# IntegratedSensor.net
KiCad netlist of a schematic drawn in EAGLE
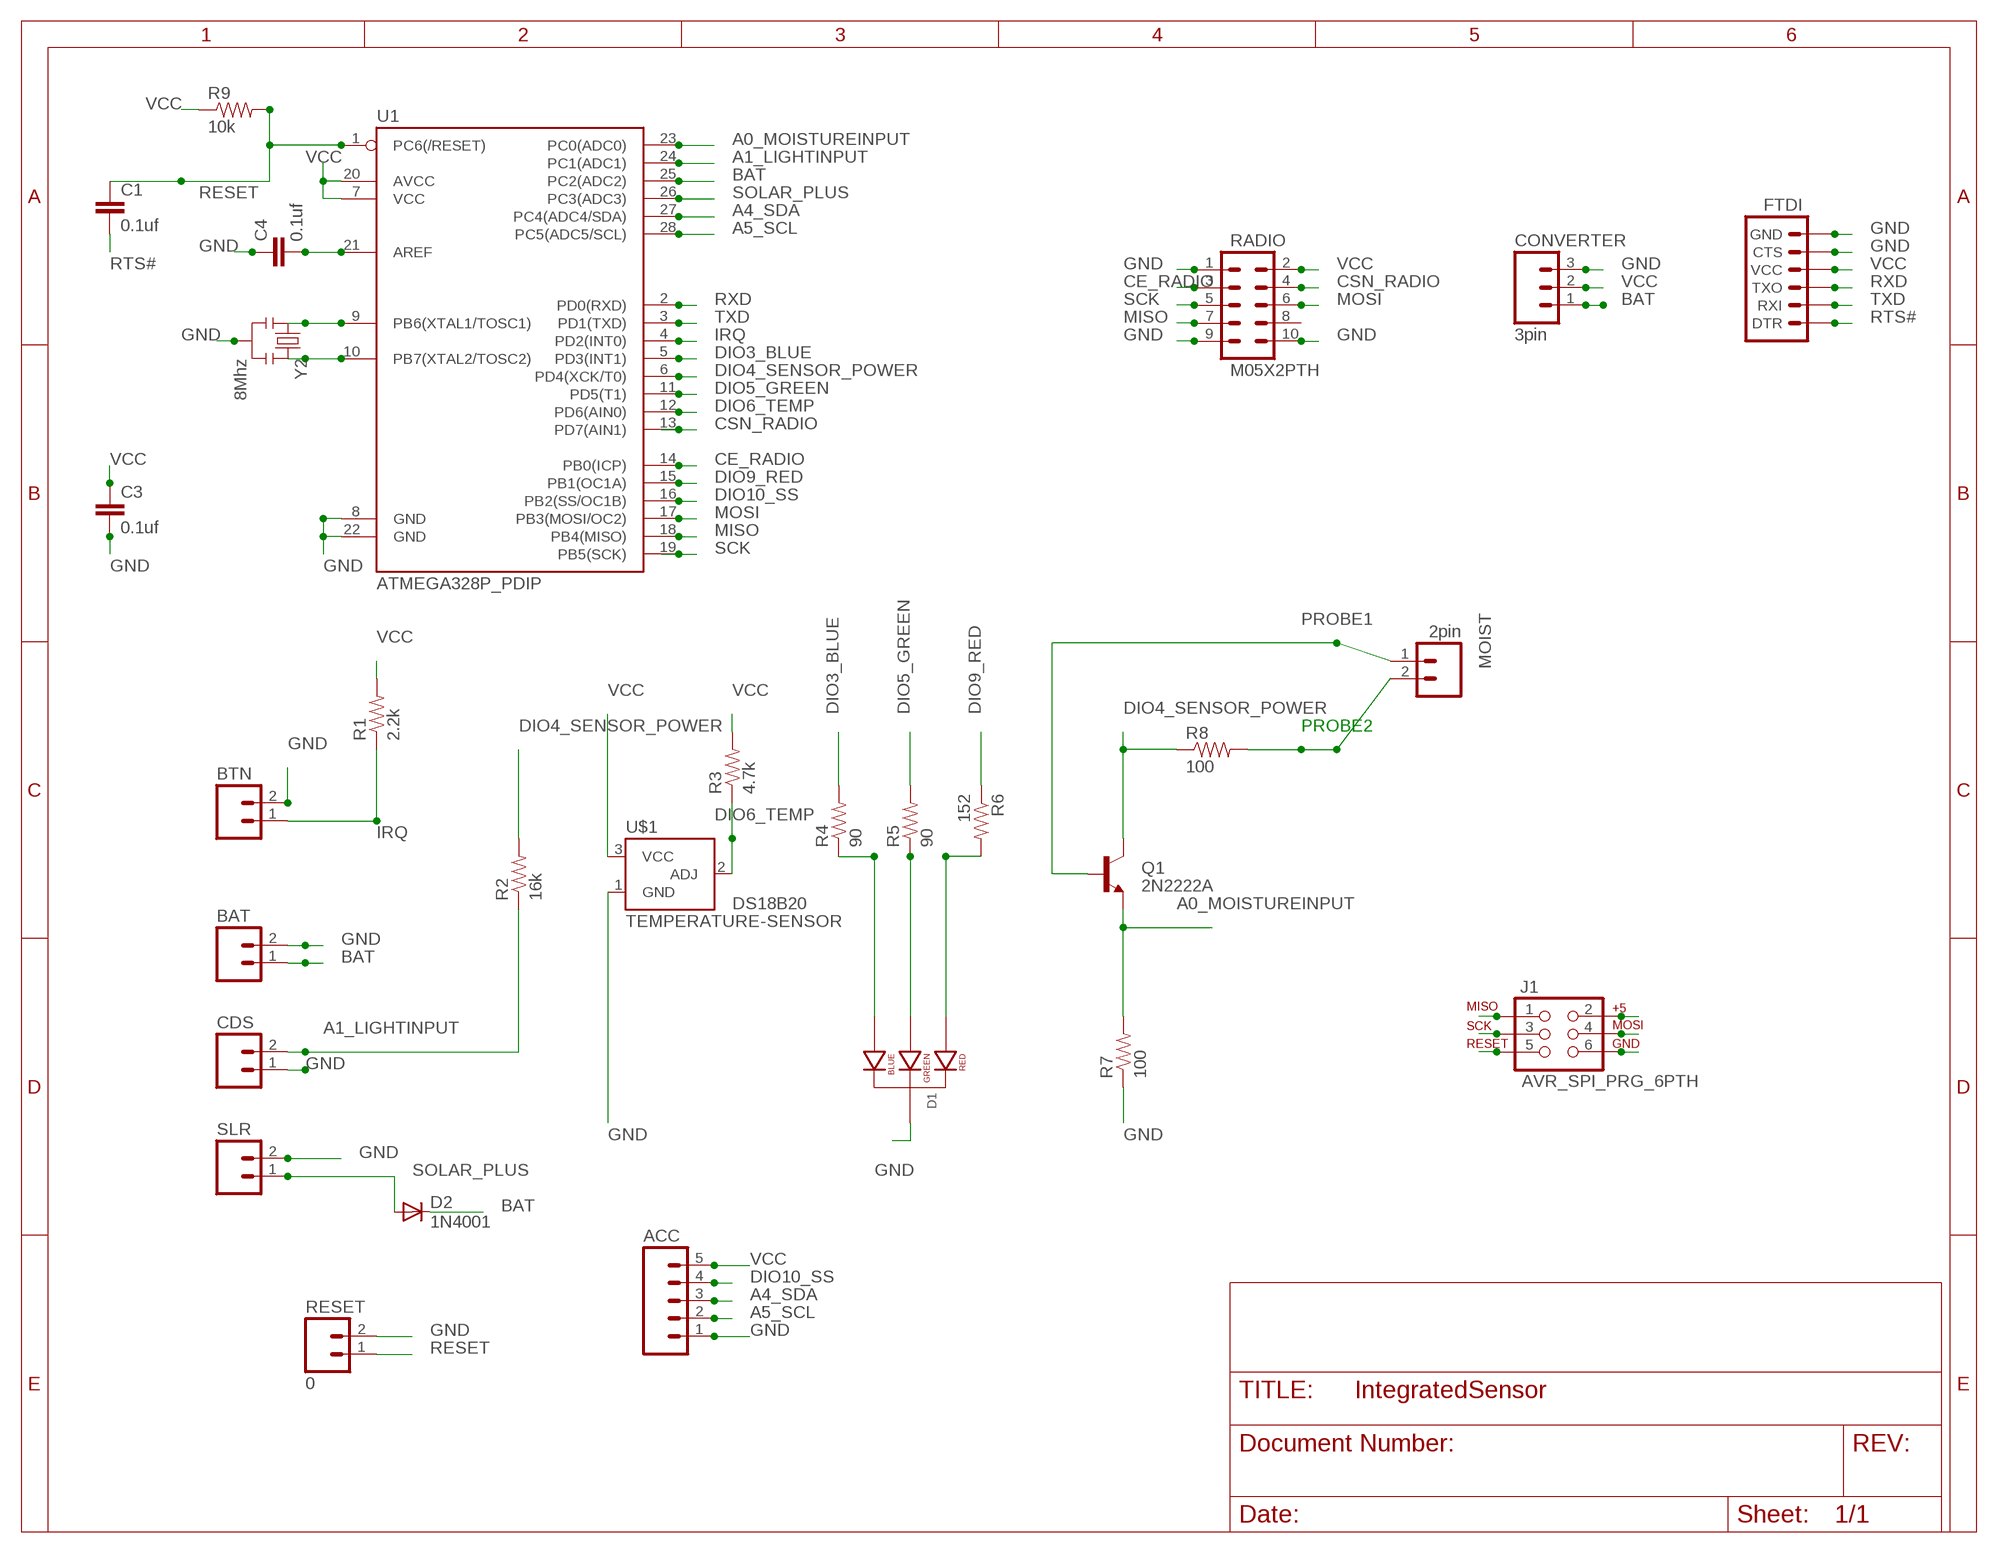
[diagram p0: schematic, sheet 1]

(export (version "E")
  (design (tool "Eeschema 10.0.6"))
  (components
    (comp (ref "ACC")
      (value "M05PTH")
      (footprint "eagle-import:1X05")
      (libsource (lib "eagle-import") (part "M05PTH"))
    )
    (comp (ref "BAT")
      (value "M02PTH")
      (footprint "eagle-import:1X02")
      (libsource (lib "eagle-import") (part "M02PTH"))
    )
    (comp (ref "BTN")
      (value "M02PTH")
      (footprint "eagle-import:1X02")
      (libsource (lib "eagle-import") (part "M02PTH"))
    )
    (comp (ref "C1")
      (value "0.1uf")
      (footprint "eagle-import:CAP-PTH-SMALL")
      (libsource (lib "eagle-import") (part "CAPPTH"))
    )
    (comp (ref "C3")
      (value "0.1uf")
      (footprint "eagle-import:CAP-PTH-SMALL")
      (libsource (lib "eagle-import") (part "CAPPTH"))
    )
    (comp (ref "C4")
      (value "0.1uf")
      (footprint "eagle-import:CAP-PTH-SMALL")
      (libsource (lib "eagle-import") (part "CAPPTH"))
    )
    (comp (ref "CDS")
      (value "M02PTH")
      (footprint "eagle-import:1X02")
      (libsource (lib "eagle-import") (part "M02PTH"))
    )
    (comp (ref "CONVERTER")
      (value "3pin")
      (footprint "eagle-import:1X03")
      (libsource (lib "eagle-import") (part "M03PTH"))
    )
    (comp (ref "D1")
      (value "LED-RGB-CC-THRUCLEAR")
      (footprint "eagle-import:LED-RGB-THRU")
      (libsource (lib "eagle-import") (part "LED-RGB-CC-THRUCLEAR"))
    )
    (comp (ref "D2")
      (value "1N4001")
      (footprint "eagle-import:DIODE-1N4001")
      (libsource (lib "eagle-import") (part "DIODEPTH"))
    )
    (comp (ref "FTDI")
      (value "ARDUINO_SERIAL_PROGRAMPTH")
      (footprint "eagle-import:1X06")
      (libsource (lib "eagle-import") (part "ARDUINO_SERIAL_PROGRAMPTH"))
    )
    (comp (ref "J1")
      (value "AVR_SPI_PRG_6PTH")
      (footprint "eagle-import:2X3")
      (libsource (lib "eagle-import") (part "AVR_SPI_PRG_6PTH"))
    )
    (comp (ref "MOIST")
      (value "2pin")
      (footprint "eagle-import:1X02")
      (libsource (lib "eagle-import") (part "M02PTH"))
    )
    (comp (ref "Q1")
      (value "2N2222A")
      (footprint "eagle-import:TO-92-AMMO")
      (libsource (lib "eagle-import") (part "TRANSISTOR_NPNTO-92-AMMO"))
    )
    (comp (ref "R1")
      (value "2.2k")
      (footprint "eagle-import:1_6W-RES")
      (libsource (lib "eagle-import") (part "RESISTORPTH-1/6W"))
    )
    (comp (ref "R2")
      (value "16k")
      (footprint "eagle-import:1_6W-RES")
      (libsource (lib "eagle-import") (part "RESISTORPTH-1/6W"))
    )
    (comp (ref "R3")
      (value "4.7k")
      (footprint "eagle-import:1_6W-RES")
      (libsource (lib "eagle-import") (part "RESISTORPTH-1/6W"))
    )
    (comp (ref "R4")
      (value "90")
      (footprint "eagle-import:1_6W-RES")
      (libsource (lib "eagle-import") (part "RESISTORPTH-1/6W"))
    )
    (comp (ref "R5")
      (value "90")
      (footprint "eagle-import:1_6W-RES")
      (libsource (lib "eagle-import") (part "RESISTORPTH-1/6W"))
    )
    (comp (ref "R6")
      (value "152")
      (footprint "eagle-import:1_6W-RES")
      (libsource (lib "eagle-import") (part "RESISTORPTH-1/6W"))
    )
    (comp (ref "R7")
      (value "100")
      (footprint "eagle-import:1_6W-RES")
      (libsource (lib "eagle-import") (part "RESISTORPTH-1/6W"))
    )
    (comp (ref "R8")
      (value "100")
      (footprint "eagle-import:1_6W-RES")
      (libsource (lib "eagle-import") (part "RESISTORPTH-1/6W"))
    )
    (comp (ref "R9")
      (value "10k")
      (footprint "eagle-import:1_6W-RES")
      (libsource (lib "eagle-import") (part "RESISTORPTH-1/6W"))
    )
    (comp (ref "RADIO")
      (value "M05X2PTH")
      (footprint "eagle-import:AVR_ICSP")
      (libsource (lib "eagle-import") (part "M05X2PTH"))
    )
    (comp (ref "RESET")
      (value "0")
      (footprint "eagle-import:1X02")
      (libsource (lib "eagle-import") (part "M02PTH"))
    )
    (comp (ref "SLR")
      (value "M02PTH")
      (footprint "eagle-import:1X02")
      (libsource (lib "eagle-import") (part "M02PTH"))
    )
    (comp (ref "U$1")
      (value "TEMPERATURE-SENSOR")
      (footprint "eagle-import:TO-92")
      (fields (field (name "PARTNAME") "DS18B20"))
      (libsource (lib "eagle-import") (part "TEMPERATURE-SENSOR"))
    )
    (comp (ref "U1")
      (value "ATMEGA328P_PDIP")
      (footprint "eagle-import:DIL28-3")
      (libsource (lib "eagle-import") (part "ATMEGA328P_PDIP"))
    )
    (comp (ref "Y2")
      (value "8Mhz")
      (footprint "eagle-import:RESONATOR-PTH")
      (libsource (lib "eagle-import") (part "RESONATORPTH"))
    )
  )
  (nets
    (net (code "1") (name "/A0_MOISTUREINPUT") (class "Default")
      (node (ref "Q1") (pin "1") (pinfunction "E_1") (pintype "passive"))
      (node (ref "R7") (pin "2") (pinfunction "2_2") (pintype "passive"))
      (node (ref "U1") (pin "23") (pinfunction "PC0(ADC0)_23") (pintype "bidirectional"))
    )
    (net (code "2") (name "/A1_LIGHTINPUT") (class "Default")
      (node (ref "CDS") (pin "2") (pinfunction "2_2") (pintype "passive"))
      (node (ref "R2") (pin "1") (pinfunction "1_1") (pintype "passive"))
      (node (ref "U1") (pin "24") (pinfunction "PC1(ADC1)_24") (pintype "bidirectional"))
    )
    (net (code "3") (name "/A4_SDA") (class "Default")
      (node (ref "ACC") (pin "3") (pinfunction "3_3") (pintype "passive"))
      (node (ref "U1") (pin "27") (pinfunction "PC4(ADC4/SDA)_27") (pintype "bidirectional"))
    )
    (net (code "4") (name "/A5_SCL") (class "Default")
      (node (ref "ACC") (pin "2") (pinfunction "2_2") (pintype "passive"))
      (node (ref "U1") (pin "28") (pinfunction "PC5(ADC5/SCL)_28") (pintype "bidirectional"))
    )
    (net (code "5") (name "/BAT") (class "Default")
      (node (ref "BAT") (pin "1") (pinfunction "1_1") (pintype "passive"))
      (node (ref "CONVERTER") (pin "1") (pinfunction "1_1") (pintype "passive"))
      (node (ref "D2") (pin "C") (pinfunction "C_C") (pintype "passive"))
      (node (ref "U1") (pin "25") (pinfunction "PC2(ADC2)_25") (pintype "bidirectional"))
    )
    (net (code "6") (name "/CE_RADIO") (class "Default")
      (node (ref "RADIO") (pin "3") (pinfunction "3_3") (pintype "passive"))
      (node (ref "U1") (pin "14") (pinfunction "PB0(ICP)_14") (pintype "bidirectional"))
    )
    (net (code "7") (name "/CSN_RADIO") (class "Default")
      (node (ref "RADIO") (pin "4") (pinfunction "4_4") (pintype "passive"))
      (node (ref "U1") (pin "13") (pinfunction "PD7(AIN1)_13") (pintype "bidirectional"))
    )
    (net (code "8") (name "/DIO3_BLUE") (class "Default")
      (node (ref "R4") (pin "2") (pinfunction "2_2") (pintype "passive"))
      (node (ref "U1") (pin "5") (pinfunction "PD3(INT1)_5") (pintype "bidirectional"))
    )
    (net (code "9") (name "/DIO4_SENSOR_POWER") (class "Default")
      (node (ref "Q1") (pin "3") (pinfunction "C_3") (pintype "passive"))
      (node (ref "R2") (pin "2") (pinfunction "2_2") (pintype "passive"))
      (node (ref "R8") (pin "1") (pinfunction "1_1") (pintype "passive"))
      (node (ref "U1") (pin "6") (pinfunction "PD4(XCK/T0)_6") (pintype "bidirectional"))
    )
    (net (code "10") (name "/DIO5_GREEN") (class "Default")
      (node (ref "R5") (pin "2") (pinfunction "2_2") (pintype "passive"))
      (node (ref "U1") (pin "11") (pinfunction "PD5(T1)_11") (pintype "bidirectional"))
    )
    (net (code "11") (name "/DIO6_TEMP") (class "Default")
      (node (ref "R3") (pin "1") (pinfunction "1_1") (pintype "passive"))
      (node (ref "U$1") (pin "2") (pinfunction "ADJ_2") (pintype "bidirectional"))
      (node (ref "U1") (pin "12") (pinfunction "PD6(AIN0)_12") (pintype "bidirectional"))
    )
    (net (code "12") (name "/DIO9_RED") (class "Default")
      (node (ref "R6") (pin "1") (pinfunction "1_1") (pintype "passive"))
      (node (ref "U1") (pin "15") (pinfunction "PB1(OC1A)_15") (pintype "bidirectional"))
    )
    (net (code "13") (name "/DIO10_SS") (class "Default")
      (node (ref "ACC") (pin "4") (pinfunction "4_4") (pintype "passive"))
      (node (ref "U1") (pin "16") (pinfunction "PB2(SS/OC1B)_16") (pintype "bidirectional"))
    )
    (net (code "14") (name "/GND") (class "Default")
      (node (ref "ACC") (pin "1") (pinfunction "1_1") (pintype "passive"))
      (node (ref "BAT") (pin "2") (pinfunction "2_2") (pintype "passive"))
      (node (ref "BTN") (pin "2") (pinfunction "2_2") (pintype "passive"))
      (node (ref "C3") (pin "2") (pinfunction "2_2") (pintype "passive"))
      (node (ref "C4") (pin "1") (pinfunction "1_1") (pintype "passive"))
      (node (ref "CDS") (pin "1") (pinfunction "1_1") (pintype "passive"))
      (node (ref "CONVERTER") (pin "3") (pinfunction "3_3") (pintype "passive"))
      (node (ref "D1") (pin "2") (pinfunction "CATHODE_2") (pintype "bidirectional"))
      (node (ref "FTDI") (pin "5") (pinfunction "CTS_5") (pintype "passive"))
      (node (ref "FTDI") (pin "6") (pinfunction "GND_6") (pintype "passive"))
      (node (ref "J1") (pin "6") (pinfunction "6_6") (pintype "passive"))
      (node (ref "R7") (pin "1") (pinfunction "1_1") (pintype "passive"))
      (node (ref "RADIO") (pin "1") (pinfunction "1_1") (pintype "passive"))
      (node (ref "RADIO") (pin "10") (pinfunction "10_10") (pintype "passive"))
      (node (ref "RADIO") (pin "9") (pinfunction "9_9") (pintype "passive"))
      (node (ref "RESET") (pin "2") (pinfunction "2_2") (pintype "passive"))
      (node (ref "SLR") (pin "2") (pinfunction "2_2") (pintype "passive"))
      (node (ref "U$1") (pin "1") (pinfunction "GND_1") (pintype "bidirectional"))
      (node (ref "U1") (pin "22") (pinfunction "GND_22") (pintype "bidirectional"))
      (node (ref "U1") (pin "8") (pinfunction "GND_8") (pintype "bidirectional"))
      (node (ref "Y2") (pin "2") (pinfunction "2_2") (pintype "passive"))
    )
    (net (code "15") (name "/IRQ") (class "Default")
      (node (ref "BTN") (pin "1") (pinfunction "1_1") (pintype "passive"))
      (node (ref "R1") (pin "1") (pinfunction "1_1") (pintype "passive"))
      (node (ref "U1") (pin "4") (pinfunction "PD2(INT0)_4") (pintype "bidirectional"))
    )
    (net (code "16") (name "/MISO") (class "Default")
      (node (ref "J1") (pin "1") (pinfunction "1_1") (pintype "passive"))
      (node (ref "RADIO") (pin "7") (pinfunction "7_7") (pintype "passive"))
      (node (ref "U1") (pin "18") (pinfunction "PB4(MISO)_18") (pintype "bidirectional"))
    )
    (net (code "17") (name "/MOSI") (class "Default")
      (node (ref "J1") (pin "4") (pinfunction "4_4") (pintype "passive"))
      (node (ref "RADIO") (pin "6") (pinfunction "6_6") (pintype "passive"))
      (node (ref "U1") (pin "17") (pinfunction "PB3(MOSI/OC2)_17") (pintype "bidirectional"))
    )
    (net (code "18") (name "/PROBE1") (class "Default")
      (node (ref "MOIST") (pin "1") (pinfunction "1_1") (pintype "passive"))
      (node (ref "Q1") (pin "2") (pinfunction "B_2") (pintype "passive"))
    )
    (net (code "19") (name "/PROBE2") (class "Default")
      (node (ref "MOIST") (pin "2") (pinfunction "2_2") (pintype "passive"))
      (node (ref "R8") (pin "2") (pinfunction "2_2") (pintype "passive"))
    )
    (net (code "20") (name "/RESET") (class "Default")
      (node (ref "C1") (pin "1") (pinfunction "1_1") (pintype "passive"))
      (node (ref "J1") (pin "5") (pinfunction "5_5") (pintype "passive"))
      (node (ref "R9") (pin "2") (pinfunction "2_2") (pintype "passive"))
      (node (ref "RESET") (pin "1") (pinfunction "1_1") (pintype "passive"))
      (node (ref "U1") (pin "1") (pinfunction "PC6(/RESET)_1") (pintype "bidirectional"))
    )
    (net (code "21") (name "/RTS#") (class "Default")
      (node (ref "C1") (pin "2") (pinfunction "2_2") (pintype "passive"))
      (node (ref "FTDI") (pin "1") (pinfunction "DTR_1") (pintype "passive"))
    )
    (net (code "22") (name "/RXD") (class "Default")
      (node (ref "FTDI") (pin "3") (pinfunction "TXO_3") (pintype "passive"))
      (node (ref "U1") (pin "2") (pinfunction "PD0(RXD)_2") (pintype "bidirectional"))
    )
    (net (code "23") (name "/SCK") (class "Default")
      (node (ref "J1") (pin "3") (pinfunction "3_3") (pintype "passive"))
      (node (ref "RADIO") (pin "5") (pinfunction "5_5") (pintype "passive"))
      (node (ref "U1") (pin "19") (pinfunction "PB5(SCK)_19") (pintype "bidirectional"))
    )
    (net (code "24") (name "/SOLAR_PLUS") (class "Default")
      (node (ref "D2") (pin "A") (pinfunction "A_A") (pintype "passive"))
      (node (ref "SLR") (pin "1") (pinfunction "1_1") (pintype "passive"))
      (node (ref "U1") (pin "26") (pinfunction "PC3(ADC3)_26") (pintype "bidirectional"))
    )
    (net (code "25") (name "/TXD") (class "Default")
      (node (ref "FTDI") (pin "2") (pinfunction "RXI_2") (pintype "passive"))
      (node (ref "U1") (pin "3") (pinfunction "PD1(TXD)_3") (pintype "bidirectional"))
    )
    (net (code "26") (name "/VCC") (class "Default")
      (node (ref "ACC") (pin "5") (pinfunction "5_5") (pintype "passive"))
      (node (ref "C3") (pin "1") (pinfunction "1_1") (pintype "passive"))
      (node (ref "CONVERTER") (pin "2") (pinfunction "2_2") (pintype "passive"))
      (node (ref "FTDI") (pin "4") (pinfunction "VCC_4") (pintype "passive"))
      (node (ref "J1") (pin "2") (pinfunction "2_2") (pintype "passive"))
      (node (ref "R1") (pin "2") (pinfunction "2_2") (pintype "passive"))
      (node (ref "R3") (pin "2") (pinfunction "2_2") (pintype "passive"))
      (node (ref "R9") (pin "1") (pinfunction "1_1") (pintype "passive"))
      (node (ref "RADIO") (pin "2") (pinfunction "2_2") (pintype "passive"))
      (node (ref "U$1") (pin "3") (pinfunction "VCC_3") (pintype "bidirectional"))
      (node (ref "U1") (pin "20") (pinfunction "AVCC_20") (pintype "bidirectional"))
      (node (ref "U1") (pin "7") (pinfunction "VCC_7") (pintype "bidirectional"))
    )
    (net (code "27") (name "Net-(D1-BLUE_CATHODE)") (class "Default")
      (node (ref "D1") (pin "4") (pinfunction "BLUE_CATHODE_4") (pintype "bidirectional"))
      (node (ref "R4") (pin "1") (pinfunction "1_1") (pintype "passive"))
    )
    (net (code "28") (name "Net-(D1-GREEN_CATHODE)") (class "Default")
      (node (ref "D1") (pin "3") (pinfunction "GREEN_CATHODE_3") (pintype "bidirectional"))
      (node (ref "R5") (pin "1") (pinfunction "1_1") (pintype "passive"))
    )
    (net (code "29") (name "Net-(D1-RED_CATHODE)") (class "Default")
      (node (ref "D1") (pin "1") (pinfunction "RED_CATHODE_1") (pintype "bidirectional"))
      (node (ref "R6") (pin "2") (pinfunction "2_2") (pintype "passive"))
    )
    (net (code "30") (name "Net-(U1-AREF)") (class "Default")
      (node (ref "C4") (pin "2") (pinfunction "2_2") (pintype "passive"))
      (node (ref "U1") (pin "21") (pinfunction "AREF_21") (pintype "bidirectional"))
    )
    (net (code "31") (name "Net-(U1-PB6(XTAL1{slash}TOSC1))") (class "Default")
      (node (ref "U1") (pin "9") (pinfunction "PB6(XTAL1/TOSC1)_9") (pintype "bidirectional"))
      (node (ref "Y2") (pin "1") (pinfunction "1_1") (pintype "passive"))
    )
    (net (code "32") (name "Net-(U1-PB7(XTAL2{slash}TOSC2))") (class "Default")
      (node (ref "U1") (pin "10") (pinfunction "PB7(XTAL2/TOSC2)_10") (pintype "bidirectional"))
      (node (ref "Y2") (pin "3") (pinfunction "3_3") (pintype "passive"))
    )
    (net (code "33") (name "unconnected-(RADIO-Pad8)") (class "Default")
      (node (ref "RADIO") (pin "8") (pinfunction "8_8") (pintype "passive"))
    )
  )
)
